# RS232.net
KiCad netlist of a schematic drawn in Altium Designer
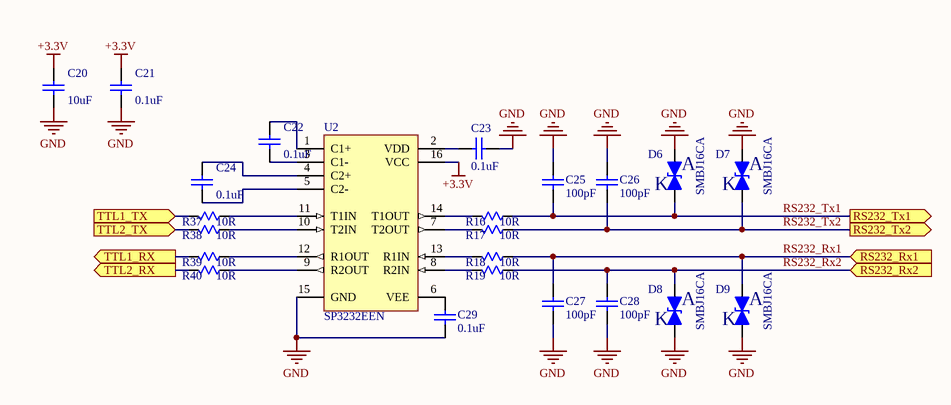
[diagram p0: 电子脚铐手持式主控板_RS232.SchDoc]

(export (version "E")
  (design (tool "Eeschema 10.0.6"))
  (components
    (comp (ref "C20")
      (value "10uF")
      (footprint "C0603")
      (description "CAP")
      (fields (field (name "PUBLISHER") "Altium Limited"))
      (libsource (lib "Passive Components Class") (part "CAP"))
    )
    (comp (ref "C21")
      (value "0.1uF")
      (footprint "C0603")
      (description "CAP")
      (fields (field (name "PUBLISHER") "Altium Limited"))
      (libsource (lib "Passive Components Class") (part "CAP"))
    )
    (comp (ref "C22")
      (value "0.1uF")
      (footprint "C0603")
      (description "CAP")
      (fields (field (name "PUBLISHER") "Altium Limited"))
      (libsource (lib "Passive Components Class") (part "CAP"))
    )
    (comp (ref "C23")
      (value "0.1uF")
      (footprint "C0603")
      (description "CAP")
      (fields (field (name "PUBLISHER") "Altium Limited"))
      (libsource (lib "Passive Components Class") (part "CAP"))
    )
    (comp (ref "C24")
      (value "0.1uF")
      (footprint "C0603")
      (description "CAP")
      (fields (field (name "PUBLISHER") "Altium Limited"))
      (libsource (lib "Passive Components Class") (part "CAP"))
    )
    (comp (ref "C25")
      (value "100pF")
      (footprint "C0603")
      (description "CAP")
      (fields (field (name "PUBLISHER") "Altium Limited"))
      (libsource (lib "Passive Components Class") (part "CAP"))
    )
    (comp (ref "C26")
      (value "100pF")
      (footprint "C0603")
      (description "CAP")
      (fields (field (name "PUBLISHER") "Altium Limited"))
      (libsource (lib "Passive Components Class") (part "CAP"))
    )
    (comp (ref "C27")
      (value "100pF")
      (footprint "C0603")
      (description "CAP")
      (fields (field (name "PUBLISHER") "Altium Limited"))
      (libsource (lib "Passive Components Class") (part "CAP"))
    )
    (comp (ref "C28")
      (value "100pF")
      (footprint "C0603")
      (description "CAP")
      (fields (field (name "PUBLISHER") "Altium Limited"))
      (libsource (lib "Passive Components Class") (part "CAP"))
    )
    (comp (ref "C29")
      (value "0.1uF")
      (footprint "C0603")
      (description "CAP")
      (fields (field (name "PUBLISHER") "Altium Limited"))
      (libsource (lib "Passive Components Class") (part "CAP"))
    )
    (comp (ref "D6") (value "SMBJ16CA") (footprint "SMB") (libsource (lib "MhSchlib") (part "BS0300N")))
    (comp (ref "D7") (value "SMBJ16CA") (footprint "SMB") (libsource (lib "MhSchlib") (part "BS0300N")))
    (comp (ref "D8") (value "SMBJ16CA") (footprint "SMB") (libsource (lib "MhSchlib") (part "BS0300N")))
    (comp (ref "D9") (value "SMBJ16CA") (footprint "SMB") (libsource (lib "MhSchlib") (part "BS0300N")))
    (comp (ref "R16")
      (value "10R")
      (footprint "R0603")
      (description "Resistor")
      (fields (field (name "PUBLISHER") "Altium Limited"))
      (libsource (lib "Temp") (part "Res"))
    )
    (comp (ref "R17")
      (value "10R")
      (footprint "R0603")
      (description "Resistor")
      (fields (field (name "PUBLISHER") "Altium Limited"))
      (libsource (lib "Temp") (part "Res"))
    )
    (comp (ref "R18")
      (value "10R")
      (footprint "R0603")
      (description "Resistor")
      (fields (field (name "PUBLISHER") "Altium Limited"))
      (libsource (lib "Temp") (part "Res"))
    )
    (comp (ref "R19")
      (value "10R")
      (footprint "R0603")
      (description "Resistor")
      (fields (field (name "PUBLISHER") "Altium Limited"))
      (libsource (lib "Temp") (part "Res"))
    )
    (comp (ref "R37")
      (value "10R")
      (footprint "R0603")
      (description "Resistor")
      (fields (field (name "PUBLISHER") "Altium Limited"))
      (libsource (lib "Temp") (part "Res"))
    )
    (comp (ref "R38")
      (value "10R")
      (footprint "R0603")
      (description "Resistor")
      (fields (field (name "PUBLISHER") "Altium Limited"))
      (libsource (lib "Temp") (part "Res"))
    )
    (comp (ref "R39")
      (value "10R")
      (footprint "R0603")
      (description "Resistor")
      (fields (field (name "PUBLISHER") "Altium Limited"))
      (libsource (lib "Temp") (part "Res"))
    )
    (comp (ref "R40")
      (value "10R")
      (footprint "R0603")
      (description "Resistor")
      (fields (field (name "PUBLISHER") "Altium Limited"))
      (libsource (lib "Temp") (part "Res"))
    )
    (comp (ref "U2")
      (value "SP3232EEN")
      (footprint "SO16")
      (description "+5V Powered, Multi-Channel RS-232 Driver/Receiver")
      (fields
        (field (name "MANUFACTURER") "Maxim")
        (field (name "PUBLISHER") "Altium Hobart Technology Centre")
      )
      (libsource (lib "Maxim Communication Transceiver") (part "MAX232ACPE"))
    )
  )
  (nets
    (net (code "1") (name "+3.3V") (class "Default")
      (node (ref "C20") (pin "1") (pinfunction "1_1") (pintype "passive"))
      (node (ref "C21") (pin "1") (pinfunction "1_1") (pintype "passive"))
      (node (ref "U2") (pin "16") (pinfunction "VCC_16") (pintype "power_in"))
    )
    (net (code "2") (name "/RS232_Rx1") (class "Default")
      (node (ref "C27") (pin "1") (pinfunction "1_1") (pintype "passive"))
      (node (ref "D9") (pin "1") (pinfunction "A_1") (pintype "passive"))
      (node (ref "R18") (pin "2") (pinfunction "2_2") (pintype "passive"))
    )
    (net (code "3") (name "/RS232_Rx2") (class "Default")
      (node (ref "C28") (pin "1") (pinfunction "1_1") (pintype "passive"))
      (node (ref "D8") (pin "1") (pinfunction "A_1") (pintype "passive"))
      (node (ref "R19") (pin "2") (pinfunction "2_2") (pintype "passive"))
    )
    (net (code "4") (name "/RS232_Tx1") (class "Default")
      (node (ref "C25") (pin "2") (pinfunction "2_2") (pintype "passive"))
      (node (ref "D6") (pin "2") (pinfunction "K_2") (pintype "passive"))
      (node (ref "R16") (pin "2") (pinfunction "2_2") (pintype "passive"))
    )
    (net (code "5") (name "/RS232_Tx2") (class "Default")
      (node (ref "C26") (pin "2") (pinfunction "2_2") (pintype "passive"))
      (node (ref "D7") (pin "2") (pinfunction "K_2") (pintype "passive"))
      (node (ref "R17") (pin "2") (pinfunction "2_2") (pintype "passive"))
    )
    (net (code "6") (name "/TTL1_RX") (class "Default")
      (node (ref "R39") (pin "1") (pinfunction "1_1") (pintype "passive"))
    )
    (net (code "7") (name "/TTL1_TX") (class "Default")
      (node (ref "R37") (pin "1") (pinfunction "1_1") (pintype "passive"))
    )
    (net (code "8") (name "/TTL2_RX") (class "Default")
      (node (ref "R40") (pin "1") (pinfunction "1_1") (pintype "passive"))
    )
    (net (code "9") (name "/TTL2_TX") (class "Default")
      (node (ref "R38") (pin "1") (pinfunction "1_1") (pintype "passive"))
    )
    (net (code "10") (name "GND") (class "Default")
      (node (ref "C20") (pin "2") (pinfunction "2_2") (pintype "passive"))
      (node (ref "C21") (pin "2") (pinfunction "2_2") (pintype "passive"))
      (node (ref "C23") (pin "1") (pinfunction "1_1") (pintype "passive"))
      (node (ref "C25") (pin "1") (pinfunction "1_1") (pintype "passive"))
      (node (ref "C26") (pin "1") (pinfunction "1_1") (pintype "passive"))
      (node (ref "C27") (pin "2") (pinfunction "2_2") (pintype "passive"))
      (node (ref "C28") (pin "2") (pinfunction "2_2") (pintype "passive"))
      (node (ref "C29") (pin "1") (pinfunction "1_1") (pintype "passive"))
      (node (ref "D6") (pin "1") (pinfunction "A_1") (pintype "passive"))
      (node (ref "D7") (pin "1") (pinfunction "A_1") (pintype "passive"))
      (node (ref "D8") (pin "2") (pinfunction "K_2") (pintype "passive"))
      (node (ref "D9") (pin "2") (pinfunction "K_2") (pintype "passive"))
      (node (ref "U2") (pin "15") (pinfunction "GND_15") (pintype "power_in"))
    )
    (net (code "11") (name "Net-(U2-C1+)") (class "Default")
      (node (ref "C22") (pin "1") (pinfunction "1_1") (pintype "passive"))
      (node (ref "U2") (pin "1") (pinfunction "C1+_1") (pintype "passive"))
    )
    (net (code "12") (name "Net-(U2-C1-)") (class "Default")
      (node (ref "C22") (pin "2") (pinfunction "2_2") (pintype "passive"))
      (node (ref "U2") (pin "3") (pinfunction "C1-_3") (pintype "passive"))
    )
    (net (code "13") (name "Net-(U2-C2+)") (class "Default")
      (node (ref "C24") (pin "1") (pinfunction "1_1") (pintype "passive"))
      (node (ref "U2") (pin "4") (pinfunction "C2+_4") (pintype "passive"))
    )
    (net (code "14") (name "Net-(U2-C2-)") (class "Default")
      (node (ref "C24") (pin "2") (pinfunction "2_2") (pintype "passive"))
      (node (ref "U2") (pin "5") (pinfunction "C2-_5") (pintype "passive"))
    )
    (net (code "15") (name "Net-(U2-R1IN)") (class "Default")
      (node (ref "R18") (pin "1") (pinfunction "1_1") (pintype "passive"))
      (node (ref "U2") (pin "13") (pinfunction "R1IN_13") (pintype "input"))
    )
    (net (code "16") (name "Net-(U2-R1OUT)") (class "Default")
      (node (ref "R39") (pin "2") (pinfunction "2_2") (pintype "passive"))
      (node (ref "U2") (pin "12") (pinfunction "R1OUT_12") (pintype "output"))
    )
    (net (code "17") (name "Net-(U2-R2IN)") (class "Default")
      (node (ref "R19") (pin "1") (pinfunction "1_1") (pintype "passive"))
      (node (ref "U2") (pin "8") (pinfunction "R2IN_8") (pintype "input"))
    )
    (net (code "18") (name "Net-(U2-R2OUT)") (class "Default")
      (node (ref "R40") (pin "2") (pinfunction "2_2") (pintype "passive"))
      (node (ref "U2") (pin "9") (pinfunction "R2OUT_9") (pintype "output"))
    )
    (net (code "19") (name "Net-(U2-T1IN)") (class "Default")
      (node (ref "R37") (pin "2") (pinfunction "2_2") (pintype "passive"))
      (node (ref "U2") (pin "11") (pinfunction "T1IN_11") (pintype "input"))
    )
    (net (code "20") (name "Net-(U2-T1OUT)") (class "Default")
      (node (ref "R16") (pin "1") (pinfunction "1_1") (pintype "passive"))
      (node (ref "U2") (pin "14") (pinfunction "T1OUT_14") (pintype "output"))
    )
    (net (code "21") (name "Net-(U2-T2IN)") (class "Default")
      (node (ref "R38") (pin "2") (pinfunction "2_2") (pintype "passive"))
      (node (ref "U2") (pin "10") (pinfunction "T2IN_10") (pintype "input"))
    )
    (net (code "22") (name "Net-(U2-T2OUT)") (class "Default")
      (node (ref "R17") (pin "1") (pinfunction "1_1") (pintype "passive"))
      (node (ref "U2") (pin "7") (pinfunction "T2OUT_7") (pintype "output"))
    )
    (net (code "23") (name "Net-(U2-VDD)") (class "Default")
      (node (ref "C23") (pin "2") (pinfunction "2_2") (pintype "passive"))
      (node (ref "U2") (pin "2") (pinfunction "VDD_2") (pintype "power_in"))
    )
    (net (code "24") (name "Net-(U2-VEE)") (class "Default")
      (node (ref "C29") (pin "2") (pinfunction "2_2") (pintype "passive"))
      (node (ref "U2") (pin "6") (pinfunction "VEE_6") (pintype "power_in"))
    )
  )
)
